# M360B.net
KiCad netlist of a schematic drawn in EAGLE
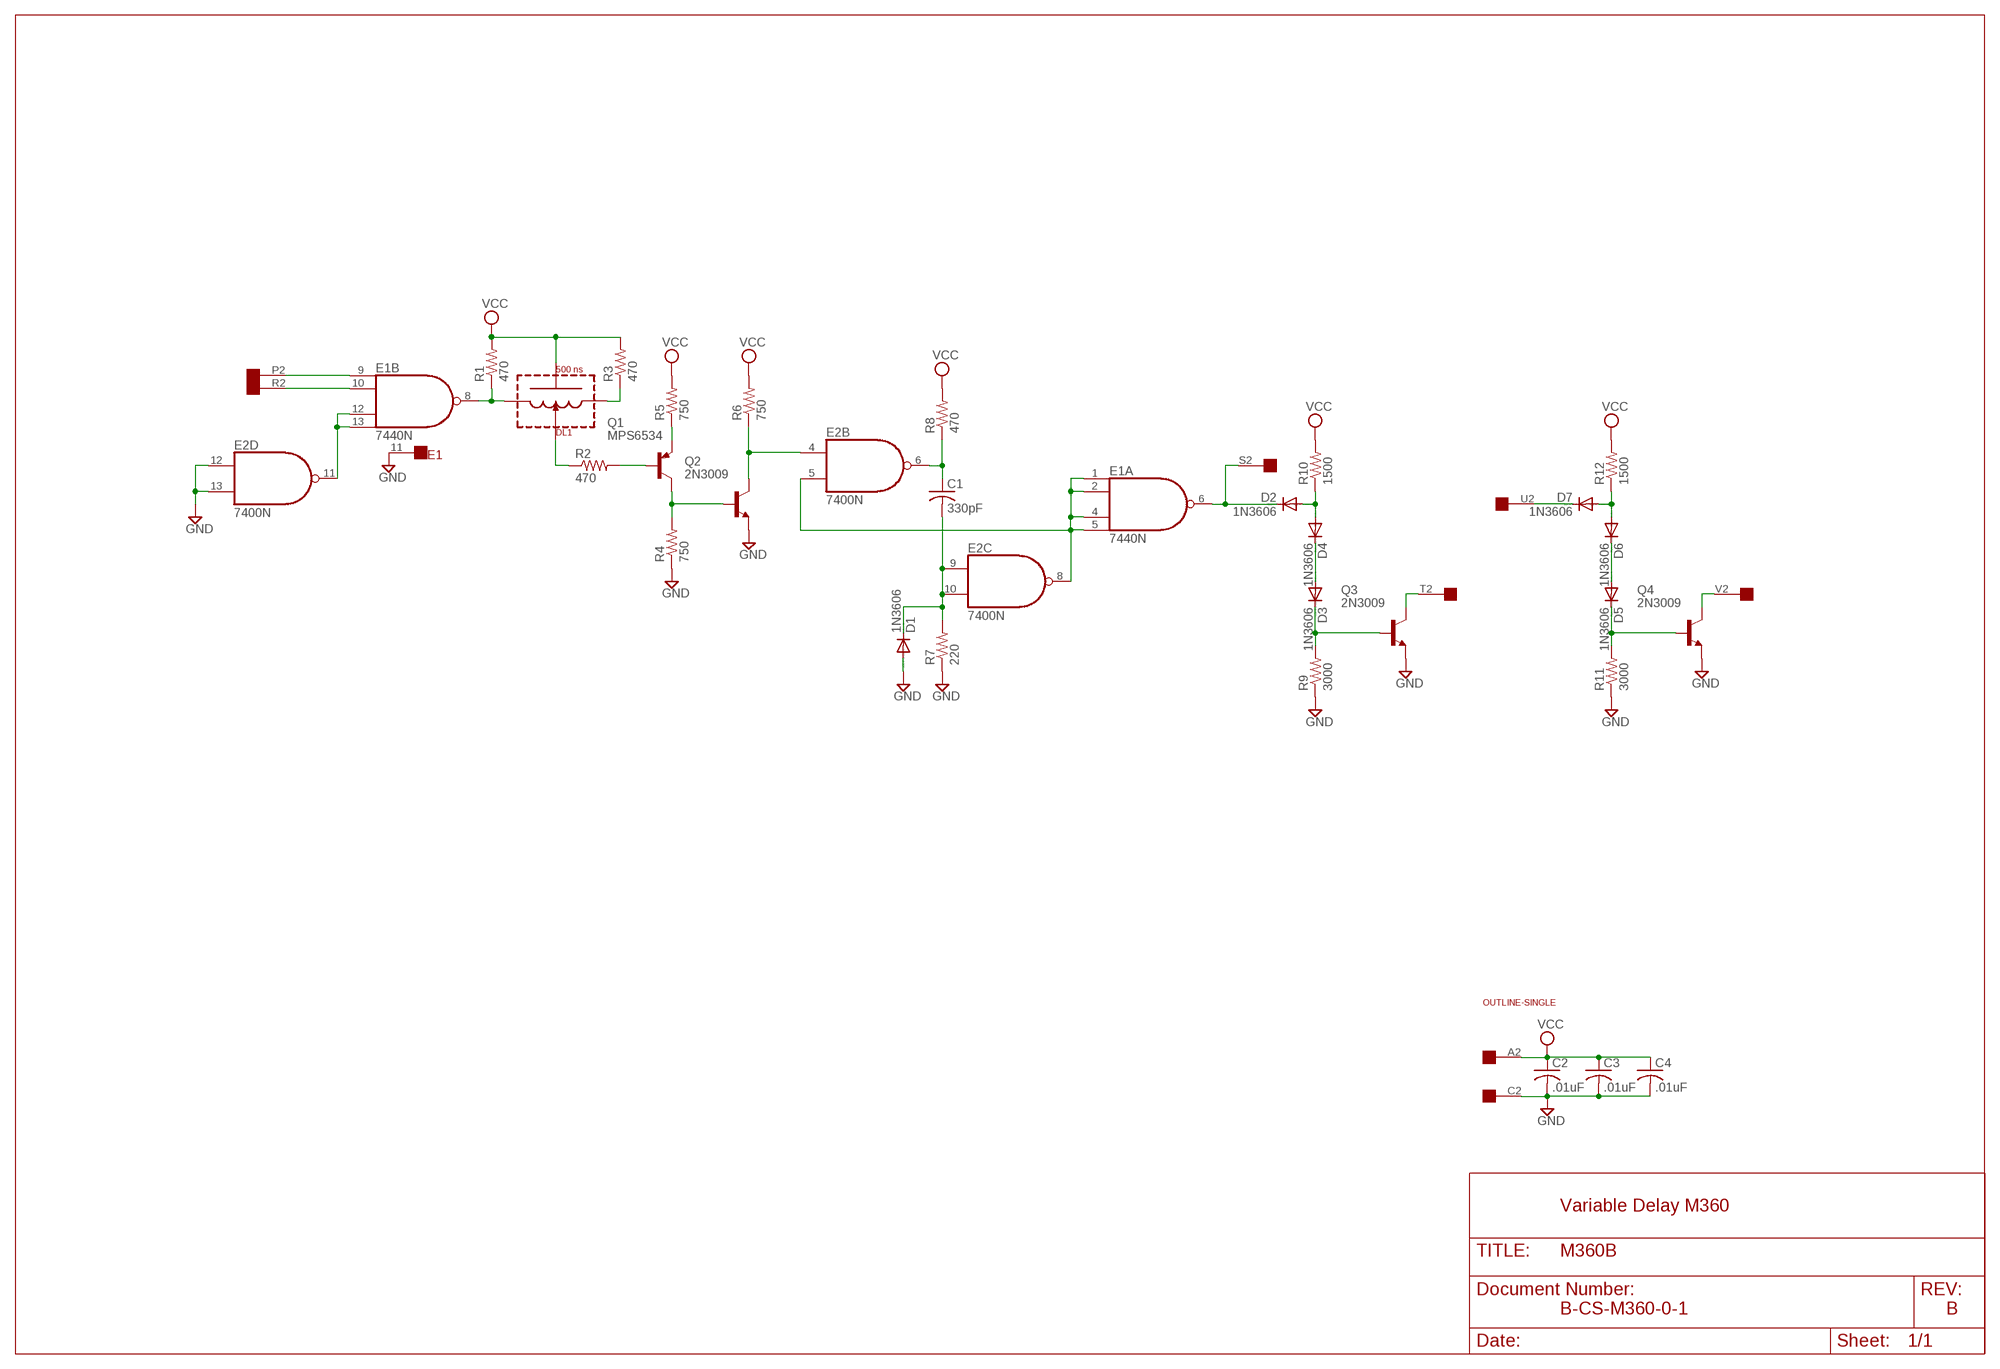
[diagram p0: schematic, sheet 1]

(export (version "E")
  (design (tool "Eeschema 10.0.6"))
  (components
    (comp (ref "C1")
      (value "330pF")
      (footprint "eagle-import:C050-025X075")
      (libsource (lib "eagle-import") (part "C-US050-025X075"))
    )
    (comp (ref "C2")
      (value ".01uF")
      (footprint "eagle-import:C050-025X075")
      (libsource (lib "eagle-import") (part "C-US050-025X075"))
    )
    (comp (ref "C3")
      (value ".01uF")
      (footprint "eagle-import:C050-025X075")
      (libsource (lib "eagle-import") (part "C-US050-025X075"))
    )
    (comp (ref "C4")
      (value ".01uF")
      (footprint "eagle-import:C050-025X075")
      (libsource (lib "eagle-import") (part "C-US050-025X075"))
    )
    (comp (ref "D1")
      (value "1N3606")
      (footprint "eagle-import:DO35-10")
      (libsource (lib "eagle-import") (part "1N4148DO35-10"))
    )
    (comp (ref "D2")
      (value "1N3606")
      (footprint "eagle-import:DO35-10")
      (libsource (lib "eagle-import") (part "1N4148DO35-10"))
    )
    (comp (ref "D3")
      (value "1N3606")
      (footprint "eagle-import:DO35-10")
      (libsource (lib "eagle-import") (part "1N4148DO35-10"))
    )
    (comp (ref "D4")
      (value "1N3606")
      (footprint "eagle-import:DO35-10")
      (libsource (lib "eagle-import") (part "1N4148DO35-10"))
    )
    (comp (ref "D5")
      (value "1N3606")
      (footprint "eagle-import:DO35-10")
      (libsource (lib "eagle-import") (part "1N4148DO35-10"))
    )
    (comp (ref "D6")
      (value "1N3606")
      (footprint "eagle-import:DO35-10")
      (libsource (lib "eagle-import") (part "1N4148DO35-10"))
    )
    (comp (ref "D7")
      (value "1N3606")
      (footprint "eagle-import:DO35-10")
      (libsource (lib "eagle-import") (part "1N4148DO35-10"))
    )
    (comp (ref "DL1")
      (value "500 ns")
      (footprint "eagle-import:DELAYLINE")
      (libsource (lib "eagle-import") (part "DELAYLINE"))
    )
    (comp (ref "E1")
      (value "7440N")
      (footprint "eagle-import:DIL14")
      (libsource (lib "eagle-import") (part "7440NS"))
    )
    (comp (ref "E2")
      (value "7400N")
      (footprint "eagle-import:DIL14")
      (libsource (lib "eagle-import") (part "7400N"))
    )
    (comp (ref "Q1")
      (value "MPS6534")
      (footprint "eagle-import:TO39")
      (libsource (lib "eagle-import") (part "2N3637"))
    )
    (comp (ref "Q2")
      (value "2N3009")
      (footprint "eagle-import:TO39")
      (libsource (lib "eagle-import") (part "2N3019"))
    )
    (comp (ref "Q3")
      (value "2N3009")
      (footprint "eagle-import:TO39")
      (libsource (lib "eagle-import") (part "2N3019"))
    )
    (comp (ref "Q4")
      (value "2N3009")
      (footprint "eagle-import:TO39")
      (libsource (lib "eagle-import") (part "2N3019"))
    )
    (comp (ref "R1")
      (value "470")
      (footprint "eagle-import:0207_10")
      (libsource (lib "eagle-import") (part "R-US_0207/10"))
    )
    (comp (ref "R2")
      (value "470")
      (footprint "eagle-import:0207_10")
      (libsource (lib "eagle-import") (part "R-US_0207/10"))
    )
    (comp (ref "R3")
      (value "470")
      (footprint "eagle-import:0207_10")
      (libsource (lib "eagle-import") (part "R-US_0207/10"))
    )
    (comp (ref "R4")
      (value "750")
      (footprint "eagle-import:0207_10")
      (libsource (lib "eagle-import") (part "R-US_0207/10"))
    )
    (comp (ref "R5")
      (value "750")
      (footprint "eagle-import:0207_10")
      (libsource (lib "eagle-import") (part "R-US_0207/10"))
    )
    (comp (ref "R6")
      (value "750")
      (footprint "eagle-import:0207_10")
      (libsource (lib "eagle-import") (part "R-US_0207/10"))
    )
    (comp (ref "R7")
      (value "220")
      (footprint "eagle-import:0207_10")
      (libsource (lib "eagle-import") (part "R-US_0207/10"))
    )
    (comp (ref "R8")
      (value "470")
      (footprint "eagle-import:0207_10")
      (libsource (lib "eagle-import") (part "R-US_0207/10"))
    )
    (comp (ref "R9")
      (value "3000")
      (footprint "eagle-import:0207_10")
      (libsource (lib "eagle-import") (part "R-US_0207/10"))
    )
    (comp (ref "R10")
      (value "1500")
      (footprint "eagle-import:0207_10")
      (libsource (lib "eagle-import") (part "R-US_0207/10"))
    )
    (comp (ref "R11")
      (value "3000")
      (footprint "eagle-import:0207_10")
      (libsource (lib "eagle-import") (part "R-US_0207/10"))
    )
    (comp (ref "R12")
      (value "1500")
      (footprint "eagle-import:0207_10")
      (libsource (lib "eagle-import") (part "R-US_0207/10"))
    )
    (comp (ref "U$1")
      (value "OUTLINE-SINGLE")
      (footprint "eagle-import:SINGLE")
      (libsource (lib "eagle-import") (part "OUTLINE-SINGLE"))
    )
    (comp (ref "U$4")
      (value "SINGLE")
      (footprint "eagle-import:EDGE-CON2")
      (libsource (lib "eagle-import") (part "SINGLE"))
    )
  )
  (nets
    (net (code "1") (name "GND") (class "Default")
      (node (ref "C2") (pin "2") (pinfunction "2_2") (pintype "passive"))
      (node (ref "C3") (pin "2") (pinfunction "2_2") (pintype "passive"))
      (node (ref "C4") (pin "2") (pinfunction "2_2") (pintype "passive"))
      (node (ref "D1") (pin "A") (pinfunction "A_A") (pintype "passive"))
      (node (ref "E1") (pin "11") (pinfunction "NC_11") (pintype "passive"))
      (node (ref "E2") (pin "12") (pinfunction "I0_12") (pintype "input"))
      (node (ref "E2") (pin "13") (pinfunction "I1_13") (pintype "input"))
      (node (ref "Q2") (pin "1") (pinfunction "E_1") (pintype "passive"))
      (node (ref "Q3") (pin "1") (pinfunction "E_1") (pintype "passive"))
      (node (ref "Q4") (pin "1") (pinfunction "E_1") (pintype "passive"))
      (node (ref "R11") (pin "1") (pinfunction "1_1") (pintype "passive"))
      (node (ref "R4") (pin "1") (pinfunction "1_1") (pintype "passive"))
      (node (ref "R7") (pin "1") (pinfunction "1_1") (pintype "passive"))
      (node (ref "R9") (pin "1") (pinfunction "1_1") (pintype "passive"))
      (node (ref "U$4") (pin "C2") (pinfunction "1_C2") (pintype "bidirectional"))
    )
    (net (code "2") (name "Net-(D2-PadA)") (class "Default")
      (node (ref "D2") (pin "A") (pinfunction "A_A") (pintype "passive"))
      (node (ref "D4") (pin "A") (pinfunction "A_A") (pintype "passive"))
      (node (ref "R10") (pin "1") (pinfunction "1_1") (pintype "passive"))
    )
    (net (code "3") (name "Net-(D3-PadA)") (class "Default")
      (node (ref "D3") (pin "A") (pinfunction "A_A") (pintype "passive"))
      (node (ref "D4") (pin "C") (pinfunction "C_C") (pintype "passive"))
    )
    (net (code "4") (name "Net-(D5-PadA)") (class "Default")
      (node (ref "D5") (pin "A") (pinfunction "A_A") (pintype "passive"))
      (node (ref "D6") (pin "C") (pinfunction "C_C") (pintype "passive"))
    )
    (net (code "5") (name "Net-(D6-PadA)") (class "Default")
      (node (ref "D6") (pin "A") (pinfunction "A_A") (pintype "passive"))
      (node (ref "D7") (pin "A") (pinfunction "A_A") (pintype "passive"))
      (node (ref "R12") (pin "1") (pinfunction "1_1") (pintype "passive"))
    )
    (net (code "6") (name "Net-(DL1-PadR)") (class "Default")
      (node (ref "DL1") (pin "R") (pinfunction "R_R") (pintype "passive"))
      (node (ref "R3") (pin "1") (pinfunction "1_1") (pintype "passive"))
    )
    (net (code "7") (name "Net-(DL1-PadV)") (class "Default")
      (node (ref "DL1") (pin "V") (pinfunction "V_V") (pintype "passive"))
      (node (ref "R2") (pin "1") (pinfunction "1_1") (pintype "passive"))
    )
    (net (code "8") (name "Net-(E1C-I0)") (class "Default")
      (node (ref "E1") (pin "1") (pinfunction "I0_1") (pintype "input"))
      (node (ref "E1") (pin "2") (pinfunction "I1_2") (pintype "input"))
      (node (ref "E1") (pin "4") (pinfunction "I2_4") (pintype "input"))
      (node (ref "E1") (pin "5") (pinfunction "I3_5") (pintype "input"))
      (node (ref "E2") (pin "5") (pinfunction "I1_5") (pintype "input"))
      (node (ref "E2") (pin "8") (pinfunction "O_8") (pintype "output"))
    )
    (net (code "9") (name "Net-(E1C-O)") (class "Default")
      (node (ref "D2") (pin "C") (pinfunction "C_C") (pintype "passive"))
      (node (ref "E1") (pin "6") (pinfunction "O_6") (pintype "output"))
      (node (ref "U$4") (pin "S2") (pinfunction "1_S2") (pintype "bidirectional"))
    )
    (net (code "10") (name "Net-(E1D-I0)") (class "Default")
      (node (ref "E1") (pin "9") (pinfunction "I0_9") (pintype "input"))
      (node (ref "U$4") (pin "P2") (pinfunction "1_P2") (pintype "bidirectional"))
    )
    (net (code "11") (name "Net-(E1D-I1)") (class "Default")
      (node (ref "E1") (pin "10") (pinfunction "I1_10") (pintype "input"))
      (node (ref "U$4") (pin "R2") (pinfunction "1_R2") (pintype "bidirectional"))
    )
    (net (code "12") (name "Net-(E1D-I2)") (class "Default")
      (node (ref "E1") (pin "12") (pinfunction "I2_12") (pintype "input"))
      (node (ref "E1") (pin "13") (pinfunction "I3_13") (pintype "input"))
      (node (ref "E2") (pin "11") (pinfunction "O_11") (pintype "output"))
    )
    (net (code "13") (name "Net-(E1D-O)") (class "Default")
      (node (ref "DL1") (pin "L") (pinfunction "L_L") (pintype "passive"))
      (node (ref "E1") (pin "8") (pinfunction "O_8") (pintype "output"))
      (node (ref "R1") (pin "1") (pinfunction "1_1") (pintype "passive"))
    )
    (net (code "14") (name "Net-(E2B-I0)") (class "Default")
      (node (ref "E2") (pin "4") (pinfunction "I0_4") (pintype "input"))
      (node (ref "Q2") (pin "3") (pinfunction "C_3") (pintype "passive"))
      (node (ref "R6") (pin "1") (pinfunction "1_1") (pintype "passive"))
    )
    (net (code "15") (name "Net-(E2B-O)") (class "Default")
      (node (ref "C1") (pin "1") (pinfunction "1_1") (pintype "passive"))
      (node (ref "E2") (pin "6") (pinfunction "O_6") (pintype "output"))
      (node (ref "R8") (pin "1") (pinfunction "1_1") (pintype "passive"))
    )
    (net (code "16") (name "Net-(E2C-I0)") (class "Default")
      (node (ref "C1") (pin "2") (pinfunction "2_2") (pintype "passive"))
      (node (ref "D1") (pin "C") (pinfunction "C_C") (pintype "passive"))
      (node (ref "E2") (pin "10") (pinfunction "I1_10") (pintype "input"))
      (node (ref "E2") (pin "9") (pinfunction "I0_9") (pintype "input"))
      (node (ref "R7") (pin "2") (pinfunction "2_2") (pintype "passive"))
    )
    (net (code "17") (name "Net-(Q1-B)") (class "Default")
      (node (ref "Q1") (pin "2") (pinfunction "B_2") (pintype "passive"))
      (node (ref "R2") (pin "2") (pinfunction "2_2") (pintype "passive"))
    )
    (net (code "18") (name "Net-(Q1-C)") (class "Default")
      (node (ref "Q1") (pin "3") (pinfunction "C_3") (pintype "passive"))
      (node (ref "Q2") (pin "2") (pinfunction "B_2") (pintype "passive"))
      (node (ref "R4") (pin "2") (pinfunction "2_2") (pintype "passive"))
    )
    (net (code "19") (name "Net-(Q1-E)") (class "Default")
      (node (ref "Q1") (pin "1") (pinfunction "E_1") (pintype "passive"))
      (node (ref "R5") (pin "1") (pinfunction "1_1") (pintype "passive"))
    )
    (net (code "20") (name "Net-(Q3-B)") (class "Default")
      (node (ref "D3") (pin "C") (pinfunction "C_C") (pintype "passive"))
      (node (ref "Q3") (pin "2") (pinfunction "B_2") (pintype "passive"))
      (node (ref "R9") (pin "2") (pinfunction "2_2") (pintype "passive"))
    )
    (net (code "21") (name "Net-(Q3-C)") (class "Default")
      (node (ref "Q3") (pin "3") (pinfunction "C_3") (pintype "passive"))
      (node (ref "U$4") (pin "T2") (pinfunction "1_T2") (pintype "bidirectional"))
    )
    (net (code "22") (name "Net-(Q4-B)") (class "Default")
      (node (ref "D5") (pin "C") (pinfunction "C_C") (pintype "passive"))
      (node (ref "Q4") (pin "2") (pinfunction "B_2") (pintype "passive"))
      (node (ref "R11") (pin "2") (pinfunction "2_2") (pintype "passive"))
    )
    (net (code "23") (name "Net-(Q4-C)") (class "Default")
      (node (ref "Q4") (pin "3") (pinfunction "C_3") (pintype "passive"))
      (node (ref "U$4") (pin "V2") (pinfunction "1_V2") (pintype "bidirectional"))
    )
    (net (code "24") (name "Net-(U$4AH-1)") (class "Default")
      (node (ref "D7") (pin "C") (pinfunction "C_C") (pintype "passive"))
      (node (ref "U$4") (pin "U2") (pinfunction "1_U2") (pintype "bidirectional"))
    )
    (net (code "25") (name "VCC") (class "Default")
      (node (ref "C2") (pin "1") (pinfunction "1_1") (pintype "passive"))
      (node (ref "C3") (pin "1") (pinfunction "1_1") (pintype "passive"))
      (node (ref "C4") (pin "1") (pinfunction "1_1") (pintype "passive"))
      (node (ref "DL1") (pin "G") (pinfunction "G_G") (pintype "passive"))
      (node (ref "R1") (pin "2") (pinfunction "2_2") (pintype "passive"))
      (node (ref "R10") (pin "2") (pinfunction "2_2") (pintype "passive"))
      (node (ref "R12") (pin "2") (pinfunction "2_2") (pintype "passive"))
      (node (ref "R3") (pin "2") (pinfunction "2_2") (pintype "passive"))
      (node (ref "R5") (pin "2") (pinfunction "2_2") (pintype "passive"))
      (node (ref "R6") (pin "2") (pinfunction "2_2") (pintype "passive"))
      (node (ref "R8") (pin "2") (pinfunction "2_2") (pintype "passive"))
      (node (ref "U$4") (pin "A2") (pinfunction "1_A2") (pintype "bidirectional"))
    )
  )
)
